# IPMC_MACP.net
KiCad netlist of a schematic drawn in Altium Designer
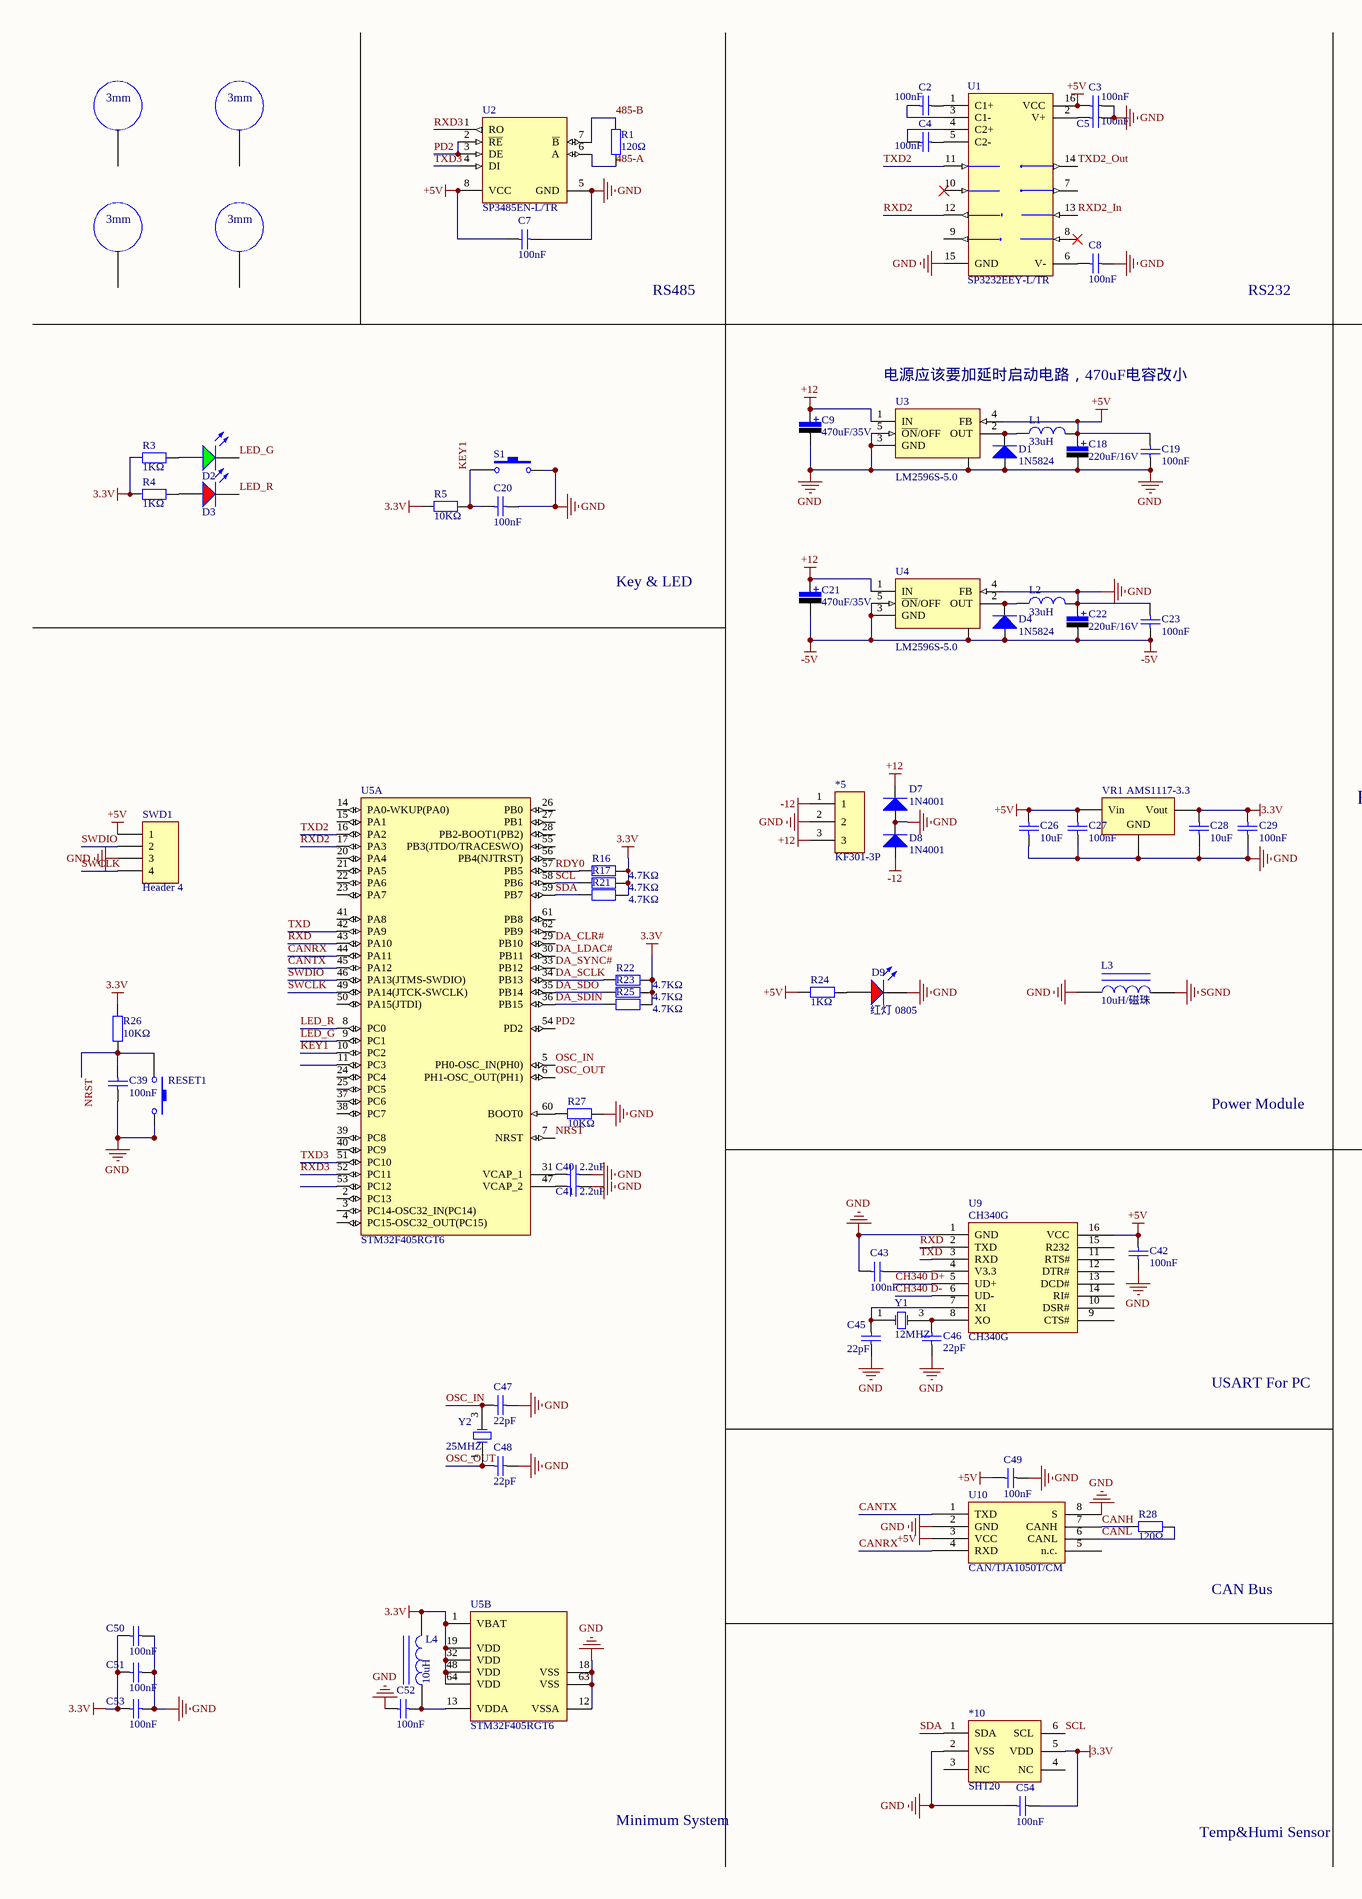
[diagram p0: IPMC_MACP.SchDoc, left]
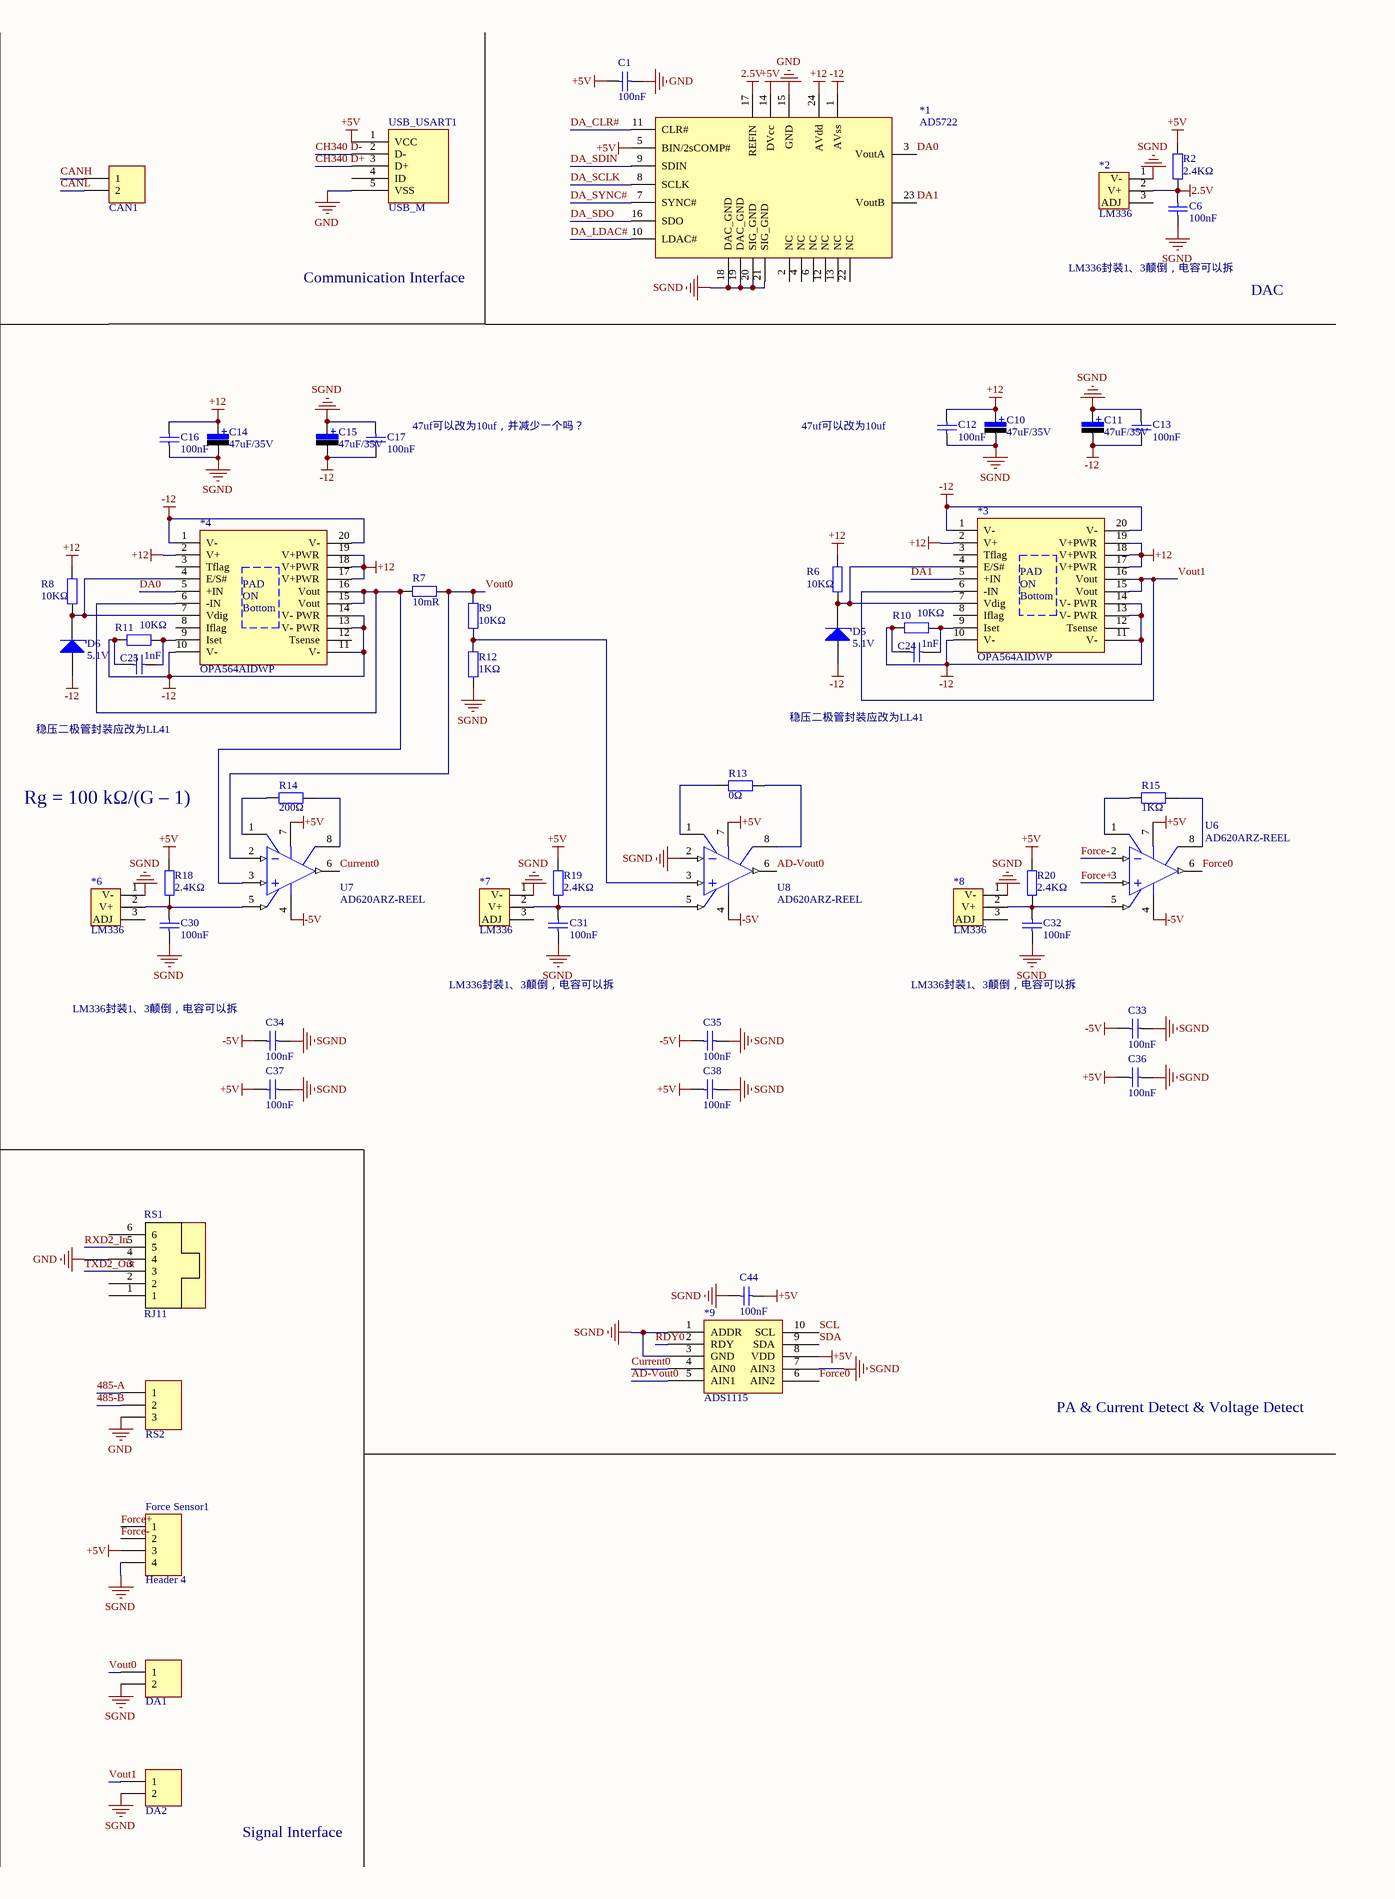
[diagram p1: IPMC_MACP.SchDoc, right]

(export (version "E")
  (design (tool "Eeschema 10.0.6"))
  (components
    (comp (ref "*1")
      (value "AD5722")
      (footprint "TSSOP24P")
      (description "双极性DAC")
      (libsource (lib "fszhang") (part "AD5722"))
    )
    (comp (ref "*2")
      (value "LM336")
      (footprint "TO-92A")
      (description "基准电压芯片2.5/5V")
      (libsource (lib "fszhang") (part "LM336"))
    )
    (comp (ref "*3")
      (value "OPA564AIDWP")
      (footprint "HSOP20")
      (description "PAD on Bottom")
      (libsource (lib "fszhang") (part "OPA564AIDWP"))
    )
    (comp (ref "*4")
      (value "OPA564AIDWP")
      (footprint "HSOP20")
      (description "PAD on Bottom")
      (libsource (lib "fszhang") (part "OPA564AIDWP"))
    )
    (comp (ref "*5")
      (value "KF301-3P")
      (footprint "KF301-3P")
      (description "蓝色端子")
      (libsource (lib "fszhang") (part "KF301-3P"))
    )
    (comp (ref "*6")
      (value "LM336")
      (footprint "TO-92A")
      (description "基准电压芯片2.5/5V")
      (libsource (lib "fszhang") (part "LM336"))
    )
    (comp (ref "*7")
      (value "LM336")
      (footprint "TO-92A")
      (description "基准电压芯片2.5/5V")
      (libsource (lib "fszhang") (part "LM336"))
    )
    (comp (ref "*8")
      (value "LM336")
      (footprint "TO-92A")
      (description "基准电压芯片2.5/5V")
      (libsource (lib "fszhang") (part "LM336"))
    )
    (comp (ref "*9") (value "ADS1115") (footprint "MSOP-UN10_N") (libsource (lib "fszhang") (part "ADS1115")))
    (comp (ref "*10") (value "SHT20") (footprint "DFN6") (libsource (lib "fszhang") (part "SHT20")))
    (comp (ref "C1")
      (value "100nF")
      (footprint "0805_C")
      (description "贴片电容")
      (libsource (lib "Miscellaneous Devices LC") (part "0805 100nF(104) 10% 50V"))
    )
    (comp (ref "C2")
      (value "100nF")
      (footprint "0805_C")
      (description "贴片电容")
      (libsource (lib "Miscellaneous Devices LC") (part "0805 100nF(104) 10% 50V"))
    )
    (comp (ref "C3")
      (value "100nF")
      (footprint "0805_C")
      (description "贴片电容")
      (libsource (lib "Miscellaneous Devices LC") (part "0805 100nF(104) 10% 50V"))
    )
    (comp (ref "C4")
      (value "100nF")
      (footprint "0805_C")
      (description "贴片电容")
      (libsource (lib "Miscellaneous Devices LC") (part "0805 100nF(104) 10% 50V"))
    )
    (comp (ref "C5")
      (value "100nF")
      (footprint "0805_C")
      (description "贴片电容")
      (libsource (lib "Miscellaneous Devices LC") (part "0805 100nF(104) 10% 50V"))
    )
    (comp (ref "C6")
      (value "100nF")
      (footprint "0805_C")
      (description "贴片电容")
      (libsource (lib "Miscellaneous Devices LC") (part "0805 100nF(104) 10% 50V"))
    )
    (comp (ref "C7")
      (value "100nF")
      (footprint "0805_C")
      (description "贴片电容")
      (libsource (lib "Miscellaneous Devices LC") (part "0805 100nF(104) 10% 50V"))
    )
    (comp (ref "C8")
      (value "100nF")
      (footprint "0805_C")
      (description "贴片电容")
      (libsource (lib "Miscellaneous Devices LC") (part "0805 100nF(104) 10% 50V"))
    )
    (comp (ref "C9")
      (value "470uF/35V")
      (footprint "C-RB-S10")
      (description "极性电解电容")
      (fields (field (name "PUBLISHER") "Altium Limited"))
      (libsource (lib "fszhang") (part "Cap Pol"))
    )
    (comp (ref "C10")
      (value "47uF/35V")
      (footprint "C-RB-S6")
      (description "极性电解电容")
      (fields (field (name "PUBLISHER") "Altium Limited"))
      (libsource (lib "fszhang") (part "Cap Pol"))
    )
    (comp (ref "C11")
      (value "47uF/35V")
      (footprint "C-RB-S6")
      (description "极性电解电容")
      (fields (field (name "PUBLISHER") "Altium Limited"))
      (libsource (lib "fszhang") (part "Cap Pol"))
    )
    (comp (ref "C12")
      (value "100nF")
      (footprint "0805_C")
      (description "贴片电容")
      (libsource (lib "Miscellaneous Devices LC") (part "0805 100nF(104) 10% 50V"))
    )
    (comp (ref "C13")
      (value "100nF")
      (footprint "0805_C")
      (description "贴片电容")
      (libsource (lib "Miscellaneous Devices LC") (part "0805 100nF(104) 10% 50V"))
    )
    (comp (ref "C14")
      (value "47uF/35V")
      (footprint "C-RB-S6")
      (description "极性电解电容")
      (fields (field (name "PUBLISHER") "Altium Limited"))
      (libsource (lib "fszhang") (part "Cap Pol"))
    )
    (comp (ref "C15")
      (value "47uF/35V")
      (footprint "C-RB-S6")
      (description "极性电解电容")
      (fields (field (name "PUBLISHER") "Altium Limited"))
      (libsource (lib "fszhang") (part "Cap Pol"))
    )
    (comp (ref "C16")
      (value "100nF")
      (footprint "0805_C")
      (description "贴片电容")
      (libsource (lib "Miscellaneous Devices LC") (part "0805 100nF(104) 10% 50V"))
    )
    (comp (ref "C17")
      (value "100nF")
      (footprint "0805_C")
      (description "贴片电容")
      (libsource (lib "Miscellaneous Devices LC") (part "0805 100nF(104) 10% 50V"))
    )
    (comp (ref "C18")
      (value "220uF/16V")
      (footprint "C-RB-S6")
      (description "极性电解电容")
      (fields (field (name "PUBLISHER") "Altium Limited"))
      (libsource (lib "fszhang") (part "Cap Pol"))
    )
    (comp (ref "C19")
      (value "100nF")
      (footprint "0805_C")
      (description "贴片电容")
      (libsource (lib "Miscellaneous Devices LC") (part "0805 100nF(104) 10% 50V"))
    )
    (comp (ref "C20")
      (value "100nF")
      (footprint "0805_C")
      (description "贴片电容")
      (libsource (lib "Miscellaneous Devices LC") (part "0805 100nF(104) 10% 50V"))
    )
    (comp (ref "C21")
      (value "470uF/35V")
      (footprint "C-RB-S10")
      (description "极性电解电容")
      (fields (field (name "PUBLISHER") "Altium Limited"))
      (libsource (lib "fszhang") (part "Cap Pol"))
    )
    (comp (ref "C22")
      (value "220uF/16V")
      (footprint "C-RB-S6")
      (description "极性电解电容")
      (fields (field (name "PUBLISHER") "Altium Limited"))
      (libsource (lib "fszhang") (part "Cap Pol"))
    )
    (comp (ref "C23")
      (value "100nF")
      (footprint "0805_C")
      (description "贴片电容")
      (libsource (lib "Miscellaneous Devices LC") (part "0805 100nF(104) 10% 50V"))
    )
    (comp (ref "C24")
      (value "1nF")
      (footprint "0805_C")
      (description "贴片电容")
      (libsource (lib "Miscellaneous Devices LC") (part "0805 1nF (102) 10% 50V"))
    )
    (comp (ref "C25")
      (value "1nF")
      (footprint "0805_C")
      (description "贴片电容")
      (libsource (lib "Miscellaneous Devices LC") (part "0805 1nF (102) 10% 50V"))
    )
    (comp (ref "C26")
      (value "10uF")
      (footprint "0805_C")
      (description "贴片电容")
      (libsource (lib "Miscellaneous Devices LC") (part "0805 10uF (106) 10% 25V"))
    )
    (comp (ref "C27")
      (value "100nF")
      (footprint "0805_C")
      (description "贴片电容")
      (libsource (lib "Miscellaneous Devices LC") (part "0805 100nF(104) 10% 50V"))
    )
    (comp (ref "C28")
      (value "10uF")
      (footprint "0805_C")
      (description "贴片电容")
      (libsource (lib "Miscellaneous Devices LC") (part "0805 10uF (106) 10% 25V"))
    )
    (comp (ref "C29")
      (value "100nF")
      (footprint "0805_C")
      (description "贴片电容")
      (libsource (lib "Miscellaneous Devices LC") (part "0805 100nF(104) 10% 50V"))
    )
    (comp (ref "C30")
      (value "100nF")
      (footprint "0805_C")
      (description "贴片电容")
      (libsource (lib "Miscellaneous Devices LC") (part "0805 100nF(104) 10% 50V"))
    )
    (comp (ref "C31")
      (value "100nF")
      (footprint "0805_C")
      (description "贴片电容")
      (libsource (lib "Miscellaneous Devices LC") (part "0805 100nF(104) 10% 50V"))
    )
    (comp (ref "C32")
      (value "100nF")
      (footprint "0805_C")
      (description "贴片电容")
      (libsource (lib "Miscellaneous Devices LC") (part "0805 100nF(104) 10% 50V"))
    )
    (comp (ref "C33")
      (value "100nF")
      (footprint "0805_C")
      (description "贴片电容")
      (libsource (lib "Miscellaneous Devices LC") (part "0805 100nF(104) 10% 50V"))
    )
    (comp (ref "C34")
      (value "100nF")
      (footprint "0805_C")
      (description "贴片电容")
      (libsource (lib "Miscellaneous Devices LC") (part "0805 100nF(104) 10% 50V"))
    )
    (comp (ref "C35")
      (value "100nF")
      (footprint "0805_C")
      (description "贴片电容")
      (libsource (lib "Miscellaneous Devices LC") (part "0805 100nF(104) 10% 50V"))
    )
    (comp (ref "C36")
      (value "100nF")
      (footprint "0805_C")
      (description "贴片电容")
      (libsource (lib "Miscellaneous Devices LC") (part "0805 100nF(104) 10% 50V"))
    )
    (comp (ref "C37")
      (value "100nF")
      (footprint "0805_C")
      (description "贴片电容")
      (libsource (lib "Miscellaneous Devices LC") (part "0805 100nF(104) 10% 50V"))
    )
    (comp (ref "C38")
      (value "100nF")
      (footprint "0805_C")
      (description "贴片电容")
      (libsource (lib "Miscellaneous Devices LC") (part "0805 100nF(104) 10% 50V"))
    )
    (comp (ref "C39")
      (value "100nF")
      (footprint "0805_C")
      (description "贴片电容")
      (libsource (lib "Miscellaneous Devices LC") (part "0805 100nF(104) 10% 50V"))
    )
    (comp (ref "C40")
      (value "2.2uF")
      (footprint "0805_C")
      (description "贴片电容")
      (libsource (lib "Miscellaneous Devices LC") (part "0805 2.2uF (225) 20% 50V"))
    )
    (comp (ref "C41")
      (value "2.2uF")
      (footprint "0805_C")
      (description "贴片电容")
      (libsource (lib "Miscellaneous Devices LC") (part "0805 2.2uF (225) 20% 50V"))
    )
    (comp (ref "C42")
      (value "100nF")
      (footprint "0805_C")
      (description "贴片电容")
      (libsource (lib "Miscellaneous Devices LC") (part "0805 100nF(104) 10% 50V"))
    )
    (comp (ref "C43")
      (value "100nF")
      (footprint "0805_C")
      (description "贴片电容")
      (libsource (lib "Miscellaneous Devices LC") (part "0805 100nF(104) 10% 50V"))
    )
    (comp (ref "C44")
      (value "100nF")
      (footprint "0805_C")
      (description "贴片电容")
      (libsource (lib "Miscellaneous Devices LC") (part "0805 100nF(104) 10% 50V"))
    )
    (comp (ref "C45")
      (value "22pF")
      (footprint "0805_C")
      (description "贴片电容")
      (libsource (lib "Miscellaneous Devices LC") (part "0805 22pF (220) 5% 50V"))
    )
    (comp (ref "C46")
      (value "22pF")
      (footprint "0805_C")
      (description "贴片电容")
      (libsource (lib "Miscellaneous Devices LC") (part "0805 22pF (220) 5% 50V"))
    )
    (comp (ref "C47")
      (value "22pF")
      (footprint "0805_C")
      (description "贴片电容")
      (libsource (lib "Miscellaneous Devices LC") (part "0805 22pF (220) 5% 50V"))
    )
    (comp (ref "C48")
      (value "22pF")
      (footprint "0805_C")
      (description "贴片电容")
      (libsource (lib "Miscellaneous Devices LC") (part "0805 22pF (220) 5% 50V"))
    )
    (comp (ref "C49")
      (value "100nF")
      (footprint "0805_C")
      (description "贴片电容")
      (libsource (lib "Miscellaneous Devices LC") (part "0805 100nF(104) 10% 50V"))
    )
    (comp (ref "C50")
      (value "100nF")
      (footprint "0805_C")
      (description "贴片电容")
      (libsource (lib "Miscellaneous Devices LC") (part "0805 100nF(104) 10% 50V"))
    )
    (comp (ref "C51")
      (value "100nF")
      (footprint "0805_C")
      (description "贴片电容")
      (libsource (lib "Miscellaneous Devices LC") (part "0805 100nF(104) 10% 50V"))
    )
    (comp (ref "C52")
      (value "100nF")
      (footprint "0805_C")
      (description "贴片电容")
      (libsource (lib "Miscellaneous Devices LC") (part "0805 100nF(104) 10% 50V"))
    )
    (comp (ref "C53")
      (value "100nF")
      (footprint "0805_C")
      (description "贴片电容")
      (libsource (lib "Miscellaneous Devices LC") (part "0805 100nF(104) 10% 50V"))
    )
    (comp (ref "C54")
      (value "100nF")
      (footprint "0805_C")
      (description "贴片电容")
      (libsource (lib "Miscellaneous Devices LC") (part "0805 100nF(104) 10% 50V"))
    )
    (comp (ref "CAN1")
      (value "Header 2")
      (footprint "HDR2X1_B1")
      (description "接插件")
      (fields (field (name "PUBLISHER") "Altium Limited"))
      (libsource (lib "fszhang") (part "Header 2"))
    )
    (comp (ref "D1")
      (value "1N5824")
      (footprint "DIODE-SMA")
      (description "二极管")
      (fields (field (name "PUBLISHER") "Altium Limited"))
      (libsource (lib "fszhang") (part "Diode"))
    )
    (comp (ref "D2")
      (value "翠绿 0805")
      (footprint "0805_LED_S1")
      (description "发光二极管")
      (libsource (lib "Miscellaneous Devices LC") (part "0805 翠绿"))
    )
    (comp (ref "D3")
      (value "红灯 0805")
      (footprint "0805_LED_S1")
      (description "发光二极管")
      (libsource (lib "Miscellaneous Devices LC") (part "0805 红灯"))
    )
    (comp (ref "D4")
      (value "1N5824")
      (footprint "DIODE-SMA")
      (description "二极管")
      (fields (field (name "PUBLISHER") "Altium Limited"))
      (libsource (lib "fszhang") (part "Diode"))
    )
    (comp (ref "D5")
      (value "5.1V")
      (footprint "DIODE-1206")
      (description "稳压二极管")
      (fields (field (name "PUBLISHER") "Altium Limited"))
      (libsource (lib "fszhang") (part "Diode-Z"))
    )
    (comp (ref "D6")
      (value "5.1V")
      (footprint "DIODE-1206")
      (description "稳压二极管")
      (fields (field (name "PUBLISHER") "Altium Limited"))
      (libsource (lib "fszhang") (part "Diode-Z"))
    )
    (comp (ref "D7")
      (value "1N4001")
      (footprint "DIODE-SMA")
      (description "二极管")
      (fields (field (name "PUBLISHER") "Altium Limited"))
      (libsource (lib "fszhang") (part "Diode"))
    )
    (comp (ref "D8")
      (value "1N4001")
      (footprint "DIODE-SMA")
      (description "二极管")
      (fields (field (name "PUBLISHER") "Altium Limited"))
      (libsource (lib "fszhang") (part "Diode"))
    )
    (comp (ref "D9")
      (value "红灯 0805")
      (footprint "0805_LED_S1")
      (description "发光二极管")
      (libsource (lib "Miscellaneous Devices LC") (part "0805 红灯"))
    )
    (comp (ref "DA1")
      (value "Header 2")
      (footprint "HDR2X1_B1")
      (description "接插件")
      (fields (field (name "PUBLISHER") "Altium Limited"))
      (libsource (lib "fszhang") (part "Header 2"))
    )
    (comp (ref "DA2")
      (value "Header 2")
      (footprint "HDR2X1_B1")
      (description "接插件")
      (fields (field (name "PUBLISHER") "Altium Limited"))
      (libsource (lib "fszhang") (part "Header 2"))
    )
    (comp (ref "Force Sensor1")
      (value "Header 4")
      (footprint "fszhang:HDR4X1_B1")
      (description "Header, 4-Pin")
      (fields (field (name "PUBLISHER") "Altium Limited"))
      (libsource (lib "Miscellaneous Connectors") (part "Header 4"))
    )
    (comp (ref "L1")
      (value "33uH")
      (footprint "L-SMD-12")
      (description "电感")
      (fields (field (name "PUBLISHER") "Altium Limited"))
      (libsource (lib "fszhang") (part "Inductor"))
    )
    (comp (ref "L2")
      (value "33uH")
      (footprint "L-SMD-12")
      (description "电感")
      (fields (field (name "PUBLISHER") "Altium Limited"))
      (libsource (lib "fszhang") (part "Inductor"))
    )
    (comp (ref "L3")
      (value "10uH/磁珠")
      (footprint "0805_L")
      (description "贴片电感")
      (libsource (lib "Miscellaneous Devices LC") (part "0805 10uH 10%"))
    )
    (comp (ref "L4")
      (value "10uH")
      (footprint "0805_L")
      (description "贴片电感")
      (libsource (lib "Miscellaneous Devices LC") (part "0805 10uH 10%"))
    )
    (comp (ref "R1")
      (value "120Ω")
      (footprint "0805_R")
      (description "贴片电阻")
      (libsource (lib "Miscellaneous Devices LC") (part "0805 120Ω (1200) 1%"))
    )
    (comp (ref "R2")
      (value "2.4KΩ")
      (footprint "0805_R")
      (description "贴片电阻")
      (libsource (lib "Miscellaneous Devices LC") (part "0805 2.4KΩ (2401) 1%"))
    )
    (comp (ref "R3")
      (value "1KΩ")
      (footprint "0805_R")
      (description "贴片电阻")
      (libsource (lib "Miscellaneous Devices LC") (part "0805 1KΩ (1001) 1%"))
    )
    (comp (ref "R4")
      (value "1KΩ")
      (footprint "0805_R")
      (description "贴片电阻")
      (libsource (lib "Miscellaneous Devices LC") (part "0805 1KΩ (1001) 1%"))
    )
    (comp (ref "R5")
      (value "10KΩ")
      (footprint "0805_R")
      (description "贴片电阻")
      (libsource (lib "") (part "0805 10KΩ (1002) 1%_1"))
    )
    (comp (ref "R6")
      (value "10KΩ")
      (footprint "0805_R")
      (description "贴片电阻")
      (libsource (lib "Miscellaneous Devices LC") (part "0805 10KΩ (1002) 1%"))
    )
    (comp (ref "R7")
      (value "10mR")
      (footprint "2512")
      (description "贴片电阻")
      (fields (field (name "PUBLISHER") "Altium Limited"))
      (libsource (lib "fszhang") (part "Res1"))
    )
    (comp (ref "R8")
      (value "10KΩ")
      (footprint "0805_R")
      (description "贴片电阻")
      (libsource (lib "Miscellaneous Devices LC") (part "0805 10KΩ (1002) 1%"))
    )
    (comp (ref "R9")
      (value "10KΩ")
      (footprint "0805_R")
      (description "贴片电阻")
      (libsource (lib "Miscellaneous Devices LC") (part "0805 20KΩ (2002) 1%"))
    )
    (comp (ref "R10")
      (value "10KΩ")
      (footprint "0805_R")
      (description "贴片电阻")
      (libsource (lib "") (part "0805 10KΩ (1002) 1%_1"))
    )
    (comp (ref "R11")
      (value "10KΩ")
      (footprint "0805_R")
      (description "贴片电阻")
      (libsource (lib "") (part "0805 10KΩ (1002) 1%_1"))
    )
    (comp (ref "R12")
      (value "1KΩ")
      (footprint "0805_R")
      (description "贴片电阻")
      (libsource (lib "Miscellaneous Devices LC") (part "0805 20KΩ (2002) 1%"))
    )
    (comp (ref "R13")
      (value "0Ω")
      (footprint "0805_R")
      (description "贴片电阻")
      (libsource (lib "Miscellaneous Devices LC") (part "0805 0Ω (0R0) 1%"))
    )
    (comp (ref "R14")
      (value "200Ω")
      (footprint "0805_R")
      (description "贴片电阻")
      (libsource (lib "Miscellaneous Devices LC") (part "0805 200Ω (2000) 1%"))
    )
    (comp (ref "R15")
      (value "1KΩ")
      (footprint "0805_R")
      (description "贴片电阻")
      (libsource (lib "Miscellaneous Devices LC") (part "0805 1KΩ (1001) 1%"))
    )
    (comp (ref "R16")
      (value "4.7KΩ")
      (footprint "0805_R")
      (description "贴片电阻")
      (libsource (lib "Miscellaneous Devices LC") (part "0805 4.7KΩ (4701) 1%"))
    )
    (comp (ref "R17")
      (value "4.7KΩ")
      (footprint "0805_R")
      (description "贴片电阻")
      (libsource (lib "Miscellaneous Devices LC") (part "0805 4.7KΩ (4701) 1%"))
    )
    (comp (ref "R18")
      (value "2.4KΩ")
      (footprint "0805_R")
      (description "贴片电阻")
      (libsource (lib "Miscellaneous Devices LC") (part "0805 2.4KΩ (2401) 1%"))
    )
    (comp (ref "R19")
      (value "2.4KΩ")
      (footprint "0805_R")
      (description "贴片电阻")
      (libsource (lib "Miscellaneous Devices LC") (part "0805 2.4KΩ (2401) 1%"))
    )
    (comp (ref "R20")
      (value "2.4KΩ")
      (footprint "0805_R")
      (description "贴片电阻")
      (libsource (lib "Miscellaneous Devices LC") (part "0805 2.4KΩ (2401) 1%"))
    )
    (comp (ref "R21")
      (value "4.7KΩ")
      (footprint "0805_R")
      (description "贴片电阻")
      (libsource (lib "Miscellaneous Devices LC") (part "0805 4.7KΩ (4701) 1%"))
    )
    (comp (ref "R22")
      (value "4.7KΩ")
      (footprint "0805_R")
      (description "贴片电阻")
      (libsource (lib "Miscellaneous Devices LC") (part "0805 4.7KΩ (4701) 1%"))
    )
    (comp (ref "R23")
      (value "4.7KΩ")
      (footprint "0805_R")
      (description "贴片电阻")
      (libsource (lib "Miscellaneous Devices LC") (part "0805 4.7KΩ (4701) 1%"))
    )
    (comp (ref "R24")
      (value "1KΩ")
      (footprint "0805_R")
      (description "贴片电阻")
      (libsource (lib "Miscellaneous Devices LC") (part "0805 1KΩ (1001) 1%"))
    )
    (comp (ref "R25")
      (value "4.7KΩ")
      (footprint "0805_R")
      (description "贴片电阻")
      (libsource (lib "Miscellaneous Devices LC") (part "0805 4.7KΩ (4701) 1%"))
    )
    (comp (ref "R26")
      (value "10KΩ")
      (footprint "0805_R")
      (description "贴片电阻")
      (libsource (lib "") (part "0805 10KΩ (1002) 1%_2"))
    )
    (comp (ref "R27")
      (value "10KΩ")
      (footprint "0805_R")
      (description "贴片电阻")
      (libsource (lib "") (part "0805 10KΩ (1002) 1%_3"))
    )
    (comp (ref "R28")
      (value "120Ω")
      (footprint "0805_R")
      (description "贴片电阻")
      (libsource (lib "") (part "0805 120Ω (1200) 1%_1"))
    )
    (comp (ref "RESET1")
      (value "SW-PB")
      (footprint "SW_PB2_A1")
      (description "微动开关")
      (fields (field (name "PUBLISHER") "Altium Limited"))
      (libsource (lib "fszhang") (part "SW-PB"))
    )
    (comp (ref "RS1") (value "RJ11") (footprint "RJ6-RJ11") (libsource (lib "fszhang") (part "RJ11")))
    (comp (ref "RS2")
      (value "Header 3")
      (footprint "HDR3X1_B1")
      (description "接插件")
      (fields (field (name "PUBLISHER") "Altium Limited"))
      (libsource (lib "fszhang") (part "Header 3"))
    )
    (comp (ref "S1")
      (value "SW-PB")
      (footprint "SW_PB2_A1")
      (description "微动开关")
      (fields (field (name "PUBLISHER") "Altium Limited"))
      (libsource (lib "fszhang") (part "SW-PB"))
    )
    (comp (ref "SWD1")
      (value "Header 4")
      (footprint "HDR1X4")
      (description "Header, 4-Pin")
      (fields (field (name "PUBLISHER") "Altium Limited"))
      (libsource (lib "Miscellaneous Connectors") (part "Header 4"))
    )
    (comp (ref "T1") (value "M3铜柱螺丝孔") (footprint "螺丝孔-3mm") (libsource (lib "fszhang") (part "M3铜柱螺丝孔")))
    (comp (ref "T2") (value "M3铜柱螺丝孔") (footprint "螺丝孔-3mm") (libsource (lib "fszhang") (part "M3铜柱螺丝孔")))
    (comp (ref "T3") (value "M3铜柱螺丝孔") (footprint "螺丝孔-3mm") (libsource (lib "fszhang") (part "M3铜柱螺丝孔")))
    (comp (ref "T4") (value "M3铜柱螺丝孔") (footprint "螺丝孔-3mm") (libsource (lib "fszhang") (part "M3铜柱螺丝孔")))
    (comp (ref "U1")
      (value "SP3232EEY-L/TR")
      (footprint "TSSOP-16")
      (description "RS232")
      (libsource (lib "Miscellaneous Devices LC") (part "SP3232EEY-L/TR"))
    )
    (comp (ref "U2")
      (value "SP3485EN-L/TR")
      (footprint "SOIC-8_150mil")
      (description "RS-485/RS-422")
      (libsource (lib "Miscellaneous Devices LC") (part "SP3485EN-L/TR"))
    )
    (comp (ref "U3")
      (value "LM2596S-5.0")
      (footprint "TO-263-5")
      (description "5V稳压芯片")
      (fields (field (name "PUBLISHER") "Altium Limited"))
      (libsource (lib "fszhang") (part "LM2596S-5.0"))
    )
    (comp (ref "U4")
      (value "LM2596S-5.0")
      (footprint "TO-263-5")
      (description "5V稳压芯片")
      (fields (field (name "PUBLISHER") "Altium Limited"))
      (libsource (lib "fszhang") (part "LM2596S-5.0"))
    )
    (comp (ref "U5")
      (value "STM32F405RGT6")
      (footprint "STM-LQFP64_L")
      (fields (field (name "MANUFACTURER") "STMicroelectronics"))
      (libsource (lib "STMicroelectronics STM32 F4") (part "STM32F405RGT6"))
    )
    (comp (ref "U6")
      (value "AD620ARZ-REEL")
      (footprint "SOIC-8_150mil")
      (description "仪放")
      (libsource (lib "Miscellaneous Devices LC") (part "AD620ARZ-REEL"))
    )
    (comp (ref "U7")
      (value "AD620ARZ-REEL")
      (footprint "SOIC-8_150mil")
      (description "仪放")
      (libsource (lib "Miscellaneous Devices LC") (part "AD620ARZ-REEL"))
    )
    (comp (ref "U8")
      (value "AD620ARZ-REEL")
      (footprint "SOIC-8_150mil")
      (description "仪放")
      (libsource (lib "Miscellaneous Devices LC") (part "AD620ARZ-REEL"))
    )
    (comp (ref "U9")
      (value "CH340G")
      (footprint "SOIC-16_150mil")
      (description "USB")
      (libsource (lib "Miscellaneous Devices LC") (part "CH340G"))
    )
    (comp (ref "U10")
      (value "CAN/TJA1050T/CM")
      (footprint "SOIC-8_150mil")
      (description "CAN")
      (libsource (lib "Miscellaneous Devices LC") (part "CAN/TJA1050T/CM"))
    )
    (comp (ref "USB_USART1")
      (value "USB_M")
      (footprint "USB_MICRO")
      (description "MicroUSB接口")
      (libsource (lib "fszhang") (part "USB_M"))
    )
    (comp (ref "VR1")
      (value "AMS1117-3.3")
      (footprint "SOT-223")
      (description "低压差线性稳压(LDO)")
      (libsource (lib "Miscellaneous Devices LC") (part "SOT-223 AMS1117-3.3"))
    )
    (comp (ref "Y1")
      (value "12MHZ")
      (footprint "SMD-3225_4P")
      (description "贴片晶振")
      (libsource (lib "Miscellaneous Devices LC") (part "SMD-3225_4P  12MHZ 20PF 10PPM"))
    )
    (comp (ref "Y2")
      (value "25MHZ")
      (footprint "SMD-3225_4P")
      (description "贴片晶振")
      (libsource (lib "Miscellaneous Devices LC") (part "SMD-3225_4P  25MHZ 12PF 10PPM"))
    )
  )
  (nets
    (net (code "1") (name "+5V") (class "Default")
      (node (ref "*1") (pin "14") (pinfunction "DVcc_14") (pintype "passive"))
      (node (ref "*1") (pin "5") (pinfunction "BIN/2sCOMP#_5") (pintype "passive"))
      (node (ref "*9") (pin "8") (pinfunction "VDD_8") (pintype "passive"))
      (node (ref "C1") (pin "2") (pinfunction "2_2") (pintype "passive"))
      (node (ref "C18") (pin "1") (pinfunction "1_1") (pintype "passive"))
      (node (ref "C19") (pin "2") (pinfunction "2_2") (pintype "passive"))
      (node (ref "C26") (pin "2") (pinfunction "2_2") (pintype "passive"))
      (node (ref "C27") (pin "2") (pinfunction "2_2") (pintype "passive"))
      (node (ref "C3") (pin "1") (pinfunction "1_1") (pintype "passive"))
      (node (ref "C36") (pin "2") (pinfunction "2_2") (pintype "passive"))
      (node (ref "C37") (pin "2") (pinfunction "2_2") (pintype "passive"))
      (node (ref "C38") (pin "2") (pinfunction "2_2") (pintype "passive"))
      (node (ref "C42") (pin "2") (pinfunction "2_2") (pintype "passive"))
      (node (ref "C44") (pin "1") (pinfunction "1_1") (pintype "passive"))
      (node (ref "C49") (pin "2") (pinfunction "2_2") (pintype "passive"))
      (node (ref "C7") (pin "2") (pinfunction "2_2") (pintype "passive"))
      (node (ref "Force Sensor1") (pin "3") (pinfunction "3_3") (pintype "passive"))
      (node (ref "L1") (pin "2") (pinfunction "2_2") (pintype "passive"))
      (node (ref "R18") (pin "2") (pinfunction "2_2") (pintype "passive"))
      (node (ref "R19") (pin "2") (pinfunction "2_2") (pintype "passive"))
      (node (ref "R2") (pin "2") (pinfunction "2_2") (pintype "passive"))
      (node (ref "R20") (pin "2") (pinfunction "2_2") (pintype "passive"))
      (node (ref "R24") (pin "1") (pinfunction "1_1") (pintype "passive"))
      (node (ref "SWD1") (pin "1") (pinfunction "1_1") (pintype "passive"))
      (node (ref "U1") (pin "16") (pinfunction "VCC_16") (pintype "power_in"))
      (node (ref "U10") (pin "3") (pinfunction "VCC_3") (pintype "passive"))
      (node (ref "U2") (pin "8") (pinfunction "VCC_8") (pintype "power_in"))
      (node (ref "U3") (pin "4") (pinfunction "FB_4") (pintype "input"))
      (node (ref "U6") (pin "7") (pinfunction "V+_7") (pintype "power_in"))
      (node (ref "U7") (pin "7") (pinfunction "V+_7") (pintype "power_in"))
      (node (ref "U8") (pin "7") (pinfunction "V+_7") (pintype "power_in"))
      (node (ref "U9") (pin "16") (pinfunction "VCC_16") (pintype "passive"))
      (node (ref "USB_USART1") (pin "1") (pinfunction "VCC_1") (pintype "passive"))
      (node (ref "VR1") (pin "3") (pinfunction "Vin_3") (pintype "passive"))
    )
    (net (code "2") (name "+12") (class "Default")
      (node (ref "*1") (pin "24") (pinfunction "AVdd_24") (pintype "passive"))
      (node (ref "*3") (pin "17") (pinfunction "V+PWR_17") (pintype "passive"))
      (node (ref "*3") (pin "18") (pinfunction "V+PWR_18") (pintype "passive"))
      (node (ref "*3") (pin "19") (pinfunction "V+PWR_19") (pintype "passive"))
      (node (ref "*3") (pin "2") (pinfunction "V+_2") (pintype "passive"))
      (node (ref "*4") (pin "17") (pinfunction "V+PWR_17") (pintype "passive"))
      (node (ref "*4") (pin "18") (pinfunction "V+PWR_18") (pintype "passive"))
      (node (ref "*4") (pin "19") (pinfunction "V+PWR_19") (pintype "passive"))
      (node (ref "*4") (pin "2") (pinfunction "V+_2") (pintype "passive"))
      (node (ref "*5") (pin "3") (pinfunction "3_3") (pintype "passive"))
      (node (ref "C10") (pin "1") (pinfunction "1_1") (pintype "passive"))
      (node (ref "C12") (pin "2") (pinfunction "2_2") (pintype "passive"))
      (node (ref "C14") (pin "1") (pinfunction "1_1") (pintype "passive"))
      (node (ref "C16") (pin "2") (pinfunction "2_2") (pintype "passive"))
      (node (ref "C21") (pin "1") (pinfunction "1_1") (pintype "passive"))
      (node (ref "C9") (pin "1") (pinfunction "1_1") (pintype "passive"))
      (node (ref "D7") (pin "2") (pinfunction "K_2") (pintype "passive"))
      (node (ref "R6") (pin "2") (pinfunction "2_2") (pintype "passive"))
      (node (ref "R8") (pin "2") (pinfunction "2_2") (pintype "passive"))
      (node (ref "U3") (pin "1") (pinfunction "IN_1") (pintype "power_in"))
      (node (ref "U4") (pin "1") (pinfunction "IN_1") (pintype "power_in"))
    )
    (net (code "3") (name "-5V") (class "Default")
      (node (ref "C21") (pin "2") (pinfunction "2_2") (pintype "passive"))
      (node (ref "C22") (pin "2") (pinfunction "2_2") (pintype "passive"))
      (node (ref "C23") (pin "1") (pinfunction "1_1") (pintype "passive"))
      (node (ref "C33") (pin "2") (pinfunction "2_2") (pintype "passive"))
      (node (ref "C34") (pin "2") (pinfunction "2_2") (pintype "passive"))
      (node (ref "C35") (pin "2") (pinfunction "2_2") (pintype "passive"))
      (node (ref "D4") (pin "1") (pinfunction "A_1") (pintype "passive"))
      (node (ref "U4") (pin "3") (pinfunction "GND_3") (pintype "power_in"))
      (node (ref "U4") (pin "5") (pinfunction "~{ON}/OFF_5") (pintype "input"))
      (node (ref "U4") (pin "6") (pinfunction "6_6") (pintype "power_in"))
      (node (ref "U6") (pin "4") (pinfunction "V-_4") (pintype "power_in"))
      (node (ref "U7") (pin "4") (pinfunction "V-_4") (pintype "power_in"))
      (node (ref "U8") (pin "4") (pinfunction "V-_4") (pintype "power_in"))
    )
    (net (code "4") (name "-12") (class "Default")
      (node (ref "*1") (pin "1") (pinfunction "AVss_1") (pintype "passive"))
      (node (ref "*3") (pin "1") (pinfunction "V-_1") (pintype "passive"))
      (node (ref "*3") (pin "10") (pinfunction "V-_10") (pintype "passive"))
      (node (ref "*3") (pin "11") (pinfunction "V-_11") (pintype "passive"))
      (node (ref "*3") (pin "13") (pinfunction "V-_PWR_13") (pintype "passive"))
      (node (ref "*3") (pin "14") (pinfunction "V-_PWR_14") (pintype "passive"))
      (node (ref "*3") (pin "20") (pinfunction "V-_20") (pintype "passive"))
      (node (ref "*4") (pin "1") (pinfunction "V-_1") (pintype "passive"))
      (node (ref "*4") (pin "10") (pinfunction "V-_10") (pintype "passive"))
      (node (ref "*4") (pin "11") (pinfunction "V-_11") (pintype "passive"))
      (node (ref "*4") (pin "13") (pinfunction "V-_PWR_13") (pintype "passive"))
      (node (ref "*4") (pin "14") (pinfunction "V-_PWR_14") (pintype "passive"))
      (node (ref "*4") (pin "20") (pinfunction "V-_20") (pintype "passive"))
      (node (ref "*5") (pin "1") (pinfunction "1_1") (pintype "passive"))
      (node (ref "C11") (pin "2") (pinfunction "2_2") (pintype "passive"))
      (node (ref "C13") (pin "2") (pinfunction "2_2") (pintype "passive"))
      (node (ref "C15") (pin "2") (pinfunction "2_2") (pintype "passive"))
      (node (ref "C17") (pin "2") (pinfunction "2_2") (pintype "passive"))
      (node (ref "C24") (pin "1") (pinfunction "1_1") (pintype "passive"))
      (node (ref "C25") (pin "1") (pinfunction "1_1") (pintype "passive"))
      (node (ref "D5") (pin "1") (pinfunction "A_1") (pintype "passive"))
      (node (ref "D6") (pin "1") (pinfunction "A_1") (pintype "passive"))
      (node (ref "D8") (pin "1") (pinfunction "A_1") (pintype "passive"))
      (node (ref "R10") (pin "1") (pinfunction "1_1") (pintype "passive"))
      (node (ref "R11") (pin "1") (pinfunction "1_1") (pintype "passive"))
    )
    (net (code "5") (name "/485-A") (class "Default")
      (node (ref "R1") (pin "1") (pinfunction "1_1") (pintype "passive"))
      (node (ref "RS2") (pin "1") (pinfunction "1_1") (pintype "passive"))
      (node (ref "U2") (pin "6") (pinfunction "A_6") (pintype "bidirectional"))
    )
    (net (code "6") (name "/485-B") (class "Default")
      (node (ref "R1") (pin "2") (pinfunction "2_2") (pintype "passive"))
      (node (ref "RS2") (pin "2") (pinfunction "2_2") (pintype "passive"))
      (node (ref "U2") (pin "7") (pinfunction "~{B}_7") (pintype "bidirectional"))
    )
    (net (code "7") (name "/AD-Vout0") (class "Default")
      (node (ref "*9") (pin "5") (pinfunction "AIN1_5") (pintype "passive"))
      (node (ref "U8") (pin "6") (pinfunction "OUT_6") (pintype "output"))
    )
    (net (code "8") (name "/CANH") (class "Default")
      (node (ref "CAN1") (pin "1") (pinfunction "1_1") (pintype "passive"))
      (node (ref "R28") (pin "1") (pinfunction "1_1") (pintype "passive"))
      (node (ref "U10") (pin "7") (pinfunction "CANH_7") (pintype "passive"))
    )
    (net (code "9") (name "/CANL") (class "Default")
      (node (ref "CAN1") (pin "2") (pinfunction "2_2") (pintype "passive"))
      (node (ref "R28") (pin "2") (pinfunction "2_2") (pintype "passive"))
      (node (ref "U10") (pin "6") (pinfunction "CANL_6") (pintype "passive"))
    )
    (net (code "10") (name "/CANRX") (class "Default")
      (node (ref "U10") (pin "4") (pinfunction "RXD_4") (pintype "passive"))
      (node (ref "U5") (pin "44") (pinfunction "PA11_44") (pintype "bidirectional"))
    )
    (net (code "11") (name "/CANTX") (class "Default")
      (node (ref "U10") (pin "1") (pinfunction "TXD_1") (pintype "passive"))
      (node (ref "U5") (pin "45") (pinfunction "PA12_45") (pintype "bidirectional"))
    )
    (net (code "12") (name "/CH340 D+") (class "Default")
      (node (ref "U9") (pin "5") (pinfunction "UD+_5") (pintype "passive"))
      (node (ref "USB_USART1") (pin "3") (pinfunction "D+_3") (pintype "passive"))
    )
    (net (code "13") (name "/CH340 D-") (class "Default")
      (node (ref "U9") (pin "6") (pinfunction "UD-_6") (pintype "passive"))
      (node (ref "USB_USART1") (pin "2") (pinfunction "D-_2") (pintype "passive"))
    )
    (net (code "14") (name "/Current0") (class "Default")
      (node (ref "*9") (pin "4") (pinfunction "AIN0_4") (pintype "passive"))
      (node (ref "U7") (pin "6") (pinfunction "OUT_6") (pintype "output"))
    )
    (net (code "15") (name "/DA0") (class "Default")
      (node (ref "*1") (pin "3") (pinfunction "VoutA_3") (pintype "passive"))
      (node (ref "*4") (pin "5") (pinfunction "+IN_5") (pintype "passive"))
    )
    (net (code "16") (name "/DA1") (class "Default")
      (node (ref "*1") (pin "23") (pinfunction "VoutB_23") (pintype "passive"))
      (node (ref "*3") (pin "5") (pinfunction "+IN_5") (pintype "passive"))
    )
    (net (code "17") (name "/DA_CLR#") (class "Default")
      (node (ref "*1") (pin "11") (pinfunction "CLR#_11") (pintype "passive"))
      (node (ref "U5") (pin "29") (pinfunction "PB10_29") (pintype "bidirectional"))
    )
    (net (code "18") (name "/DA_LDAC#") (class "Default")
      (node (ref "*1") (pin "10") (pinfunction "LDAC#_10") (pintype "passive"))
      (node (ref "U5") (pin "30") (pinfunction "PB11_30") (pintype "bidirectional"))
    )
    (net (code "19") (name "/DA_SCLK") (class "Default")
      (node (ref "*1") (pin "8") (pinfunction "SCLK_8") (pintype "passive"))
      (node (ref "R22") (pin "1") (pinfunction "1_1") (pintype "passive"))
      (node (ref "U5") (pin "34") (pinfunction "PB13_34") (pintype "bidirectional"))
    )
    (net (code "20") (name "/DA_SDIN") (class "Default")
      (node (ref "*1") (pin "9") (pinfunction "SDIN_9") (pintype "passive"))
      (node (ref "R25") (pin "1") (pinfunction "1_1") (pintype "passive"))
      (node (ref "U5") (pin "36") (pinfunction "PB15_36") (pintype "bidirectional"))
    )
    (net (code "21") (name "/DA_SDO") (class "Default")
      (node (ref "*1") (pin "16") (pinfunction "SDO_16") (pintype "passive"))
      (node (ref "R23") (pin "1") (pinfunction "1_1") (pintype "passive"))
      (node (ref "U5") (pin "35") (pinfunction "PB14_35") (pintype "bidirectional"))
    )
    (net (code "22") (name "/DA_SYNC#") (class "Default")
      (node (ref "*1") (pin "7") (pinfunction "SYNC#_7") (pintype "passive"))
      (node (ref "U5") (pin "33") (pinfunction "PB12_33") (pintype "bidirectional"))
    )
    (net (code "23") (name "/Force+") (class "Default")
      (node (ref "Force Sensor1") (pin "1") (pinfunction "1_1") (pintype "passive"))
      (node (ref "U6") (pin "3") (pinfunction "+IN_3") (pintype "input"))
    )
    (net (code "24") (name "/Force-") (class "Default")
      (node (ref "Force Sensor1") (pin "2") (pinfunction "2_2") (pintype "passive"))
      (node (ref "U6") (pin "2") (pinfunction "-IN_2") (pintype "input"))
    )
    (net (code "25") (name "/Force0") (class "Default")
      (node (ref "*9") (pin "6") (pinfunction "AIN2_6") (pintype "passive"))
      (node (ref "U6") (pin "6") (pinfunction "OUT_6") (pintype "output"))
    )
    (net (code "26") (name "/KEY1") (class "Default")
      (node (ref "C20") (pin "1") (pinfunction "1_1") (pintype "passive"))
      (node (ref "R5") (pin "2") (pinfunction "2_2") (pintype "passive"))
      (node (ref "S1") (pin "1") (pinfunction "1_1") (pintype "passive"))
      (node (ref "U5") (pin "10") (pinfunction "PC2_10") (pintype "bidirectional"))
    )
    (net (code "27") (name "/LED_G") (class "Default")
      (node (ref "D2") (pin "K") (pinfunction "K_K") (pintype "passive"))
      (node (ref "U5") (pin "9") (pinfunction "PC1_9") (pintype "bidirectional"))
    )
    (net (code "28") (name "/LED_R") (class "Default")
      (node (ref "D3") (pin "K") (pinfunction "K_K") (pintype "passive"))
      (node (ref "U5") (pin "8") (pinfunction "PC0_8") (pintype "bidirectional"))
    )
    (net (code "29") (name "/NRST") (class "Default")
      (node (ref "C39") (pin "1") (pinfunction "1_1") (pintype "passive"))
      (node (ref "R26") (pin "2") (pinfunction "2_2") (pintype "passive"))
      (node (ref "RESET1") (pin "1") (pinfunction "1_1") (pintype "passive"))
      (node (ref "U5") (pin "7") (pinfunction "NRST_7") (pintype "bidirectional"))
    )
    (net (code "30") (name "/OSC_IN") (class "Default")
      (node (ref "C47") (pin "2") (pinfunction "2_2") (pintype "passive"))
      (node (ref "U5") (pin "5") (pinfunction "PH0-OSC_IN(PH0)_5") (pintype "bidirectional"))
      (node (ref "Y2") (pin "3") (pinfunction "OSC2_3") (pintype "passive"))
    )
    (net (code "31") (name "/OSC_OUT") (class "Default")
      (node (ref "C48") (pin "2") (pinfunction "2_2") (pintype "passive"))
      (node (ref "U5") (pin "6") (pinfunction "PH1-OSC_OUT(PH1)_6") (pintype "bidirectional"))
      (node (ref "Y2") (pin "1") (pinfunction "OSC1_1") (pintype "passive"))
    )
    (net (code "32") (name "/PD2") (class "Default")
      (node (ref "U2") (pin "2") (pinfunction "~{RE}_2") (pintype "input"))
      (node (ref "U2") (pin "3") (pinfunction "DE_3") (pintype "input"))
      (node (ref "U5") (pin "54") (pinfunction "PD2_54") (pintype "bidirectional"))
    )
    (net (code "33") (name "/RDY0") (class "Default")
      (node (ref "*9") (pin "2") (pinfunction "RDY_2") (pintype "passive"))
      (node (ref "R16") (pin "1") (pinfunction "1_1") (pintype "passive"))
      (node (ref "U5") (pin "57") (pinfunction "PB5_57") (pintype "bidirectional"))
    )
    (net (code "34") (name "/RXD") (class "Default")
      (node (ref "U5") (pin "43") (pinfunction "PA10_43") (pintype "bidirectional"))
      (node (ref "U9") (pin "2") (pinfunction "TXD_2") (pintype "passive"))
    )
    (net (code "35") (name "/RXD2") (class "Default")
      (node (ref "U1") (pin "12") (pinfunction "R1OUT_12") (pintype "output"))
      (node (ref "U5") (pin "17") (pinfunction "PA3_17") (pintype "bidirectional"))
    )
    (net (code "36") (name "/RXD2_In") (class "Default")
      (node (ref "RS1") (pin "5") (pinfunction "5_5") (pintype "passive"))
      (node (ref "U1") (pin "13") (pinfunction "R1IN_13") (pintype "input"))
    )
    (net (code "37") (name "/RXD3") (class "Default")
      (node (ref "U2") (pin "1") (pinfunction "RO_1") (pintype "output"))
      (node (ref "U5") (pin "52") (pinfunction "PC11_52") (pintype "bidirectional"))
    )
    (net (code "38") (name "/SCL") (class "Default")
      (node (ref "*10") (pin "6") (pinfunction "SCL_6") (pintype "passive"))
      (node (ref "*9") (pin "10") (pinfunction "SCL_10") (pintype "passive"))
      (node (ref "R17") (pin "1") (pinfunction "1_1") (pintype "passive"))
      (node (ref "U5") (pin "58") (pinfunction "PB6_58") (pintype "bidirectional"))
    )
    (net (code "39") (name "/SDA") (class "Default")
      (node (ref "*10") (pin "1") (pinfunction "SDA_1") (pintype "passive"))
      (node (ref "*9") (pin "9") (pinfunction "SDA_9") (pintype "passive"))
      (node (ref "R21") (pin "1") (pinfunction "1_1") (pintype "passive"))
      (node (ref "U5") (pin "59") (pinfunction "PB7_59") (pintype "bidirectional"))
    )
    (net (code "40") (name "/SWCLK") (class "Default")
      (node (ref "SWD1") (pin "4") (pinfunction "4_4") (pintype "passive"))
      (node (ref "U5") (pin "49") (pinfunction "PA14(JTCK-SWCLK)_49") (pintype "bidirectional"))
    )
    (net (code "41") (name "/SWDIO") (class "Default")
      (node (ref "SWD1") (pin "2") (pinfunction "2_2") (pintype "passive"))
      (node (ref "U5") (pin "46") (pinfunction "PA13(JTMS-SWDIO)_46") (pintype "bidirectional"))
    )
    (net (code "42") (name "/TXD") (class "Default")
      (node (ref "U5") (pin "42") (pinfunction "PA9_42") (pintype "bidirectional"))
      (node (ref "U9") (pin "3") (pinfunction "RXD_3") (pintype "passive"))
    )
    (net (code "43") (name "/TXD2") (class "Default")
      (node (ref "U1") (pin "11") (pinfunction "T1IN_11") (pintype "input"))
      (node (ref "U5") (pin "16") (pinfunction "PA2_16") (pintype "bidirectional"))
    )
    (net (code "44") (name "/TXD2_Out") (class "Default")
      (node (ref "RS1") (pin "3") (pinfunction "3_3") (pintype "passive"))
      (node (ref "U1") (pin "14") (pinfunction "T1OUT_14") (pintype "output"))
    )
    (net (code "45") (name "/TXD3") (class "Default")
      (node (ref "U2") (pin "4") (pinfunction "DI_4") (pintype "input"))
      (node (ref "U5") (pin "51") (pinfunction "PC10_51") (pintype "bidirectional"))
    )
    (net (code "46") (name "/Vout0") (class "Default")
      (node (ref "DA1") (pin "1") (pinfunction "1_1") (pintype "passive"))
      (node (ref "R7") (pin "2") (pinfunction "2_2") (pintype "passive"))
      (node (ref "R9") (pin "1") (pinfunction "1_1") (pintype "passive"))
      (node (ref "U7") (pin "2") (pinfunction "-IN_2") (pintype "input"))
    )
    (net (code "47") (name "/Vout1") (class "Default")
      (node (ref "*3") (pin "15") (pinfunction "Vout_15") (pintype "passive"))
      (node (ref "*3") (pin "16") (pinfunction "Vout_16") (pintype "passive"))
      (node (ref "*3") (pin "6") (pinfunction "-IN_6") (pintype "passive"))
      (node (ref "DA2") (pin "1") (pinfunction "1_1") (pintype "passive"))
    )
    (net (code "48") (name "2.5V") (class "Default")
      (node (ref "*1") (pin "17") (pinfunction "REFIN_17") (pintype "passive"))
      (node (ref "*2") (pin "2") (pinfunction "V+_2") (pintype "passive"))
      (node (ref "C6") (pin "2") (pinfunction "2_2") (pintype "passive"))
      (node (ref "R2") (pin "1") (pinfunction "1_1") (pintype "passive"))
    )
    (net (code "49") (name "3.3V") (class "Default")
      (node (ref "*10") (pin "5") (pinfunction "VDD_5") (pintype "passive"))
      (node (ref "C28") (pin "2") (pinfunction "2_2") (pintype "passive"))
      (node (ref "C29") (pin "2") (pinfunction "2_2") (pintype "passive"))
      (node (ref "C50") (pin "1") (pinfunction "1_1") (pintype "passive"))
      (node (ref "C51") (pin "1") (pinfunction "1_1") (pintype "passive"))
      (node (ref "C53") (pin "1") (pinfunction "1_1") (pintype "passive"))
      (node (ref "C54") (pin "1") (pinfunction "1_1") (pintype "passive"))
      (node (ref "L4") (pin "2") (pinfunction "2_2") (pintype "passive"))
      (node (ref "R16") (pin "2") (pinfunction "2_2") (pintype "passive"))
      (node (ref "R17") (pin "2") (pinfunction "2_2") (pintype "passive"))
      (node (ref "R21") (pin "2") (pinfunction "2_2") (pintype "passive"))
      (node (ref "R22") (pin "2") (pinfunction "2_2") (pintype "passive"))
      (node (ref "R23") (pin "2") (pinfunction "2_2") (pintype "passive"))
      (node (ref "R25") (pin "2") (pinfunction "2_2") (pintype "passive"))
      (node (ref "R26") (pin "1") (pinfunction "1_1") (pintype "passive"))
      (node (ref "R3") (pin "1") (pinfunction "1_1") (pintype "passive"))
      (node (ref "R4") (pin "1") (pinfunction "1_1") (pintype "passive"))
      (node (ref "R5") (pin "1") (pinfunction "1_1") (pintype "passive"))
      (node (ref "U5") (pin "1") (pinfunction "VBAT_1") (pintype "power_in"))
      (node (ref "U5") (pin "19") (pinfunction "VDD_19") (pintype "power_in"))
      (node (ref "U5") (pin "32") (pinfunction "VDD_32") (pintype "power_in"))
      (node (ref "U5") (pin "48") (pinfunction "VDD_48") (pintype "power_in"))
      (node (ref "U5") (pin "64") (pinfunction "VDD_64") (pintype "power_in"))
      (node (ref "VR1") (pin "2") (pinfunction "Vout_2") (pintype "passive"))
    )
    (net (code "50") (name "GND") (class "Default")
      (node (ref "*1") (pin "15") (pinfunction "GND_15") (pintype "passive"))
      (node (ref "*10") (pin "2") (pinfunction "VSS_2") (pintype "passive"))
      (node (ref "*5") (pin "2") (pinfunction "2_2") (pintype "passive"))
      (node (ref "C1") (pin "1") (pinfunction "1_1") (pintype "passive"))
      (node (ref "C18") (pin "2") (pinfunction "2_2") (pintype "passive"))
      (node (ref "C19") (pin "1") (pinfunction "1_1") (pintype "passive"))
      (node (ref "C20") (pin "2") (pinfunction "2_2") (pintype "passive"))
      (node (ref "C22") (pin "1") (pinfunction "1_1") (pintype "passive"))
      (node (ref "C23") (pin "2") (pinfunction "2_2") (pintype "passive"))
      (node (ref "C26") (pin "1") (pinfunction "1_1") (pintype "passive"))
      (node (ref "C27") (pin "1") (pinfunction "1_1") (pintype "passive"))
      (node (ref "C28") (pin "1") (pinfunction "1_1") (pintype "passive"))
      (node (ref "C29") (pin "1") (pinfunction "1_1") (pintype "passive"))
      (node (ref "C3") (pin "2") (pinfunction "2_2") (pintype "passive"))
      (node (ref "C39") (pin "2") (pinfunction "2_2") (pintype "passive"))
      (node (ref "C40") (pin "2") (pinfunction "2_2") (pintype "passive"))
      (node (ref "C41") (pin "2") (pinfunction "2_2") (pintype "passive"))
      (node (ref "C42") (pin "1") (pinfunction "1_1") (pintype "passive"))
      (node (ref "C43") (pin "2") (pinfunction "2_2") (pintype "passive"))
      (node (ref "C45") (pin "1") (pinfunction "1_1") (pintype "passive"))
      (node (ref "C46") (pin "1") (pinfunction "1_1") (pintype "passive"))
      (node (ref "C47") (pin "1") (pinfunction "1_1") (pintype "passive"))
      (node (ref "C48") (pin "1") (pinfunction "1_1") (pintype "passive"))
      (node (ref "C49") (pin "1") (pinfunction "1_1") (pintype "passive"))
      (node (ref "C5") (pin "2") (pinfunction "2_2") (pintype "passive"))
      (node (ref "C50") (pin "2") (pinfunction "2_2") (pintype "passive"))
      (node (ref "C51") (pin "2") (pinfunction "2_2") (pintype "passive"))
      (node (ref "C52") (pin "2") (pinfunction "2_2") (pintype "passive"))
      (node (ref "C53") (pin "2") (pinfunction "2_2") (pintype "passive"))
      (node (ref "C54") (pin "2") (pinfunction "2_2") (pintype "passive"))
      (node (ref "C7") (pin "1") (pinfunction "1_1") (pintype "passive"))
      (node (ref "C8") (pin "2") (pinfunction "2_2") (pintype "passive"))
      (node (ref "C9") (pin "2") (pinfunction "2_2") (pintype "passive"))
      (node (ref "D1") (pin "1") (pinfunction "A_1") (pintype "passive"))
      (node (ref "D7") (pin "1") (pinfunction "A_1") (pintype "passive"))
      (node (ref "D8") (pin "2") (pinfunction "K_2") (pintype "passive"))
      (node (ref "D9") (pin "K") (pinfunction "K_K") (pintype "passive"))
      (node (ref "L2") (pin "2") (pinfunction "2_2") (pintype "passive"))
      (node (ref "L3") (pin "1") (pinfunction "1_1") (pintype "passive"))
      (node (ref "R27") (pin "1") (pinfunction "1_1") (pintype "passive"))
      (node (ref "RESET1") (pin "2") (pinfunction "2_2") (pintype "passive"))
      (node (ref "RS1") (pin "4") (pinfunction "4_4") (pintype "passive"))
      (node (ref "RS2") (pin "3") (pinfunction "3_3") (pintype "passive"))
      (node (ref "S1") (pin "2") (pinfunction "2_2") (pintype "passive"))
      (node (ref "SWD1") (pin "3") (pinfunction "3_3") (pintype "passive"))
      (node (ref "U1") (pin "15") (pinfunction "GND_15") (pintype "power_in"))
      (node (ref "U10") (pin "2") (pinfunction "GND_2") (pintype "passive"))
      (node (ref "U10") (pin "8") (pinfunction "S_8") (pintype "passive"))
      (node (ref "U2") (pin "5") (pinfunction "GND_5") (pintype "power_in"))
      (node (ref "U3") (pin "3") (pinfunction "GND_3") (pintype "power_in"))
      (node (ref "U3") (pin "5") (pinfunction "~{ON}/OFF_5") (pintype "input"))
      (node (ref "U3") (pin "6") (pinfunction "6_6") (pintype "power_in"))
      (node (ref "U4") (pin "4") (pinfunction "FB_4") (pintype "input"))
      (node (ref "U5") (pin "12") (pinfunction "VSSA_12") (pintype "power_in"))
      (node (ref "U5") (pin "18") (pinfunction "VSS_18") (pintype "power_in"))
      (node (ref "U5") (pin "63") (pinfunction "VSS_63") (pintype "power_in"))
      (node (ref "U9") (pin "1") (pinfunction "GND_1") (pintype "passive"))
      (node (ref "USB_USART1") (pin "5") (pinfunction "VSS_5") (pintype "passive"))
      (node (ref "VR1") (pin "1") (pinfunction "GND_1") (pintype "passive"))
    )
    (net (code "51") (name "Net-(*3-E{slash}S#)") (class "Default")
      (node (ref "*3") (pin "4") (pinfunction "E/S#_4") (pintype "passive"))
      (node (ref "*3") (pin "7") (pinfunction "Vdig_7") (pintype "passive"))
      (node (ref "D5") (pin "2") (pinfunction "K_2") (pintype "passive"))
      (node (ref "R6") (pin "1") (pinfunction "1_1") (pintype "passive"))
    )
    (net (code "52") (name "Net-(*3-Iset)") (class "Default")
      (node (ref "*3") (pin "9") (pinfunction "Iset_9") (pintype "passive"))
      (node (ref "C24") (pin "2") (pinfunction "2_2") (pintype "passive"))
      (node (ref "R10") (pin "2") (pinfunction "2_2") (pintype "passive"))
    )
    (net (code "53") (name "Net-(*4--IN)") (class "Default")
      (node (ref "*4") (pin "15") (pinfunction "Vout_15") (pintype "passive"))
      (node (ref "*4") (pin "16") (pinfunction "Vout_16") (pintype "passive"))
      (node (ref "*4") (pin "6") (pinfunction "-IN_6") (pintype "passive"))
      (node (ref "R7") (pin "1") (pinfunction "1_1") (pintype "passive"))
      (node (ref "U7") (pin "3") (pinfunction "+IN_3") (pintype "input"))
    )
    (net (code "54") (name "Net-(*4-E{slash}S#)") (class "Default")
      (node (ref "*4") (pin "4") (pinfunction "E/S#_4") (pintype "passive"))
      (node (ref "*4") (pin "7") (pinfunction "Vdig_7") (pintype "passive"))
      (node (ref "D6") (pin "2") (pinfunction "K_2") (pintype "passive"))
      (node (ref "R8") (pin "1") (pinfunction "1_1") (pintype "passive"))
    )
    (net (code "55") (name "Net-(*4-Iset)") (class "Default")
      (node (ref "*4") (pin "9") (pinfunction "Iset_9") (pintype "passive"))
      (node (ref "C25") (pin "2") (pinfunction "2_2") (pintype "passive"))
      (node (ref "R11") (pin "2") (pinfunction "2_2") (pintype "passive"))
    )
    (net (code "56") (name "Net-(*6-V+)") (class "Default")
      (node (ref "*6") (pin "2") (pinfunction "V+_2") (pintype "passive"))
      (node (ref "C30") (pin "2") (pinfunction "2_2") (pintype "passive"))
      (node (ref "R18") (pin "1") (pinfunction "1_1") (pintype "passive"))
      (node (ref "U7") (pin "5") (pinfunction "REF_5") (pintype "input"))
    )
    (net (code "57") (name "Net-(*7-V+)") (class "Default")
      (node (ref "*7") (pin "2") (pinfunction "V+_2") (pintype "passive"))
      (node (ref "C31") (pin "2") (pinfunction "2_2") (pintype "passive"))
      (node (ref "R19") (pin "1") (pinfunction "1_1") (pintype "passive"))
      (node (ref "U8") (pin "5") (pinfunction "REF_5") (pintype "input"))
    )
    (net (code "58") (name "Net-(*8-V+)") (class "Default")
      (node (ref "*8") (pin "2") (pinfunction "V+_2") (pintype "passive"))
      (node (ref "C32") (pin "2") (pinfunction "2_2") (pintype "passive"))
      (node (ref "R20") (pin "1") (pinfunction "1_1") (pintype "passive"))
      (node (ref "U6") (pin "5") (pinfunction "REF_5") (pintype "input"))
    )
    (net (code "59") (name "Net-(D1-K)") (class "Default")
      (node (ref "D1") (pin "2") (pinfunction "K_2") (pintype "passive"))
      (node (ref "L1") (pin "1") (pinfunction "1_1") (pintype "passive"))
      (node (ref "U3") (pin "2") (pinfunction "OUT_2") (pintype "power_in"))
    )
    (net (code "60") (name "Net-(D2-PadA)") (class "Default")
      (node (ref "D2") (pin "A") (pinfunction "A_A") (pintype "passive"))
      (node (ref "R3") (pin "2") (pinfunction "2_2") (pintype "passive"))
    )
    (net (code "61") (name "Net-(D3-PadA)") (class "Default")
      (node (ref "D3") (pin "A") (pinfunction "A_A") (pintype "passive"))
      (node (ref "R4") (pin "2") (pinfunction "2_2") (pintype "passive"))
    )
    (net (code "62") (name "Net-(D4-K)") (class "Default")
      (node (ref "D4") (pin "2") (pinfunction "K_2") (pintype "passive"))
      (node (ref "L2") (pin "1") (pinfunction "1_1") (pintype "passive"))
      (node (ref "U4") (pin "2") (pinfunction "OUT_2") (pintype "power_in"))
    )
    (net (code "63") (name "Net-(D9-PadA)") (class "Default")
      (node (ref "D9") (pin "A") (pinfunction "A_A") (pintype "passive"))
      (node (ref "R24") (pin "2") (pinfunction "2_2") (pintype "passive"))
    )
    (net (code "64") (name "Net-(R13-Pad1)") (class "Default")
      (node (ref "R13") (pin "1") (pinfunction "1_1") (pintype "passive"))
      (node (ref "U8") (pin "1") (pinfunction "RG_1") (pintype "passive"))
    )
    (net (code "65") (name "Net-(R13-Pad2)") (class "Default")
      (node (ref "R13") (pin "2") (pinfunction "2_2") (pintype "passive"))
      (node (ref "U8") (pin "8") (pinfunction "RG_8") (pintype "passive"))
    )
    (net (code "66") (name "Net-(R14-Pad1)") (class "Default")
      (node (ref "R14") (pin "1") (pinfunction "1_1") (pintype "passive"))
      (node (ref "U7") (pin "1") (pinfunction "RG_1") (pintype "passive"))
    )
    (net (code "67") (name "Net-(R14-Pad2)") (class "Default")
      (node (ref "R14") (pin "2") (pinfunction "2_2") (pintype "passive"))
      (node (ref "U7") (pin "8") (pinfunction "RG_8") (pintype "passive"))
    )
    (net (code "68") (name "Net-(R15-Pad1)") (class "Default")
      (node (ref "R15") (pin "1") (pinfunction "1_1") (pintype "passive"))
      (node (ref "U6") (pin "1") (pinfunction "RG_1") (pintype "passive"))
    )
    (net (code "69") (name "Net-(R15-Pad2)") (class "Default")
      (node (ref "R15") (pin "2") (pinfunction "2_2") (pintype "passive"))
      (node (ref "U6") (pin "8") (pinfunction "RG_8") (pintype "passive"))
    )
    (net (code "70") (name "Net-(U1-C1+)") (class "Default")
      (node (ref "C2") (pin "2") (pinfunction "2_2") (pintype "passive"))
      (node (ref "U1") (pin "1") (pinfunction "C1+_1") (pintype "passive"))
    )
    (net (code "71") (name "Net-(U1-C1-)") (class "Default")
      (node (ref "C2") (pin "1") (pinfunction "1_1") (pintype "passive"))
      (node (ref "U1") (pin "3") (pinfunction "C1-_3") (pintype "passive"))
    )
    (net (code "72") (name "Net-(U1-C2+)") (class "Default")
      (node (ref "C4") (pin "1") (pinfunction "1_1") (pintype "passive"))
      (node (ref "U1") (pin "4") (pinfunction "C2+_4") (pintype "passive"))
    )
    (net (code "73") (name "Net-(U1-C2-)") (class "Default")
      (node (ref "C4") (pin "2") (pinfunction "2_2") (pintype "passive"))
      (node (ref "U1") (pin "5") (pinfunction "C2-_5") (pintype "passive"))
    )
    (net (code "74") (name "Net-(U1-V+)") (class "Default")
      (node (ref "C5") (pin "1") (pinfunction "1_1") (pintype "passive"))
      (node (ref "U1") (pin "2") (pinfunction "V+_2") (pintype "power_in"))
    )
    (net (code "75") (name "Net-(U1-V-)") (class "Default")
      (node (ref "C8") (pin "1") (pinfunction "1_1") (pintype "passive"))
      (node (ref "U1") (pin "6") (pinfunction "V-_6") (pintype "power_in"))
    )
    (net (code "76") (name "Net-(U5A-BOOT0)") (class "Default")
      (node (ref "R27") (pin "2") (pinfunction "2_2") (pintype "passive"))
      (node (ref "U5") (pin "60") (pinfunction "BOOT0_60") (pintype "input"))
    )
    (net (code "77") (name "Net-(U5A-VCAP_1)") (class "Default")
      (node (ref "C40") (pin "1") (pinfunction "1_1") (pintype "passive"))
      (node (ref "U5") (pin "31") (pinfunction "VCAP_1_31") (pintype "power_in"))
    )
    (net (code "78") (name "Net-(U5A-VCAP_2)") (class "Default")
      (node (ref "C41") (pin "1") (pinfunction "1_1") (pintype "passive"))
      (node (ref "U5") (pin "47") (pinfunction "VCAP_2_47") (pintype "power_in"))
    )
    (net (code "79") (name "Net-(U5B-VDDA)") (class "Default")
      (node (ref "C52") (pin "1") (pinfunction "1_1") (pintype "passive"))
      (node (ref "L4") (pin "1") (pinfunction "1_1") (pintype "passive"))
      (node (ref "U5") (pin "13") (pinfunction "VDDA_13") (pintype "power_in"))
    )
    (net (code "80") (name "Net-(U8-+IN)") (class "Default")
      (node (ref "R12") (pin "1") (pinfunction "1_1") (pintype "passive"))
      (node (ref "R9") (pin "2") (pinfunction "2_2") (pintype "passive"))
      (node (ref "U8") (pin "3") (pinfunction "+IN_3") (pintype "input"))
    )
    (net (code "81") (name "Net-(U9-V3.3)") (class "Default")
      (node (ref "C43") (pin "1") (pinfunction "1_1") (pintype "passive"))
      (node (ref "U9") (pin "4") (pinfunction "V3.3_4") (pintype "passive"))
    )
    (net (code "82") (name "Net-(U9-XI)") (class "Default")
      (node (ref "C45") (pin "2") (pinfunction "2_2") (pintype "passive"))
      (node (ref "U9") (pin "7") (pinfunction "XI_7") (pintype "passive"))
      (node (ref "Y1") (pin "1") (pinfunction "OSC1_1") (pintype "passive"))
    )
    (net (code "83") (name "Net-(U9-XO)") (class "Default")
      (node (ref "C46") (pin "2") (pinfunction "2_2") (pintype "passive"))
      (node (ref "U9") (pin "8") (pinfunction "XO_8") (pintype "passive"))
      (node (ref "Y1") (pin "3") (pinfunction "OSC2_3") (pintype "passive"))
    )
    (net (code "84") (name "SGND") (class "Default")
      (node (ref "*1") (pin "18") (pinfunction "DAC_GND_18") (pintype "passive"))
      (node (ref "*1") (pin "19") (pinfunction "DAC_GND_19") (pintype "passive"))
      (node (ref "*1") (pin "20") (pinfunction "SIG_GND_20") (pintype "passive"))
      (node (ref "*1") (pin "21") (pinfunction "SIG_GND_21") (pintype "passive"))
      (node (ref "*2") (pin "1") (pinfunction "V-_1") (pintype "passive"))
      (node (ref "*6") (pin "1") (pinfunction "V-_1") (pintype "passive"))
      (node (ref "*7") (pin "1") (pinfunction "V-_1") (pintype "passive"))
      (node (ref "*8") (pin "1") (pinfunction "V-_1") (pintype "passive"))
      (node (ref "*9") (pin "1") (pinfunction "ADDR_1") (pintype "passive"))
      (node (ref "*9") (pin "3") (pinfunction "GND_3") (pintype "passive"))
      (node (ref "*9") (pin "7") (pinfunction "AIN3_7") (pintype "passive"))
      (node (ref "C10") (pin "2") (pinfunction "2_2") (pintype "passive"))
      (node (ref "C11") (pin "1") (pinfunction "1_1") (pintype "passive"))
      (node (ref "C12") (pin "1") (pinfunction "1_1") (pintype "passive"))
      (node (ref "C13") (pin "1") (pinfunction "1_1") (pintype "passive"))
      (node (ref "C14") (pin "2") (pinfunction "2_2") (pintype "passive"))
      (node (ref "C15") (pin "1") (pinfunction "1_1") (pintype "passive"))
      (node (ref "C16") (pin "1") (pinfunction "1_1") (pintype "passive"))
      (node (ref "C17") (pin "1") (pinfunction "1_1") (pintype "passive"))
      (node (ref "C30") (pin "1") (pinfunction "1_1") (pintype "passive"))
      (node (ref "C31") (pin "1") (pinfunction "1_1") (pintype "passive"))
      (node (ref "C32") (pin "1") (pinfunction "1_1") (pintype "passive"))
      (node (ref "C33") (pin "1") (pinfunction "1_1") (pintype "passive"))
      (node (ref "C34") (pin "1") (pinfunction "1_1") (pintype "passive"))
      (node (ref "C35") (pin "1") (pinfunction "1_1") (pintype "passive"))
      (node (ref "C36") (pin "1") (pinfunction "1_1") (pintype "passive"))
      (node (ref "C37") (pin "1") (pinfunction "1_1") (pintype "passive"))
      (node (ref "C38") (pin "1") (pinfunction "1_1") (pintype "passive"))
      (node (ref "C44") (pin "2") (pinfunction "2_2") (pintype "passive"))
      (node (ref "C6") (pin "1") (pinfunction "1_1") (pintype "passive"))
      (node (ref "DA1") (pin "2") (pinfunction "2_2") (pintype "passive"))
      (node (ref "DA2") (pin "2") (pinfunction "2_2") (pintype "passive"))
      (node (ref "Force Sensor1") (pin "4") (pinfunction "4_4") (pintype "passive"))
      (node (ref "L3") (pin "2") (pinfunction "2_2") (pintype "passive"))
      (node (ref "R12") (pin "2") (pinfunction "2_2") (pintype "passive"))
      (node (ref "U8") (pin "2") (pinfunction "-IN_2") (pintype "input"))
    )
    (net (code "85") (name "unconnected-(*1-NC-Pad2)") (class "Default")
      (node (ref "*1") (pin "2") (pinfunction "NC_2") (pintype "passive"))
    )
    (net (code "86") (name "unconnected-(*1-NC-Pad4)") (class "Default")
      (node (ref "*1") (pin "4") (pinfunction "NC_4") (pintype "passive"))
    )
    (net (code "87") (name "unconnected-(*1-NC-Pad6)") (class "Default")
      (node (ref "*1") (pin "6") (pinfunction "NC_6") (pintype "passive"))
    )
    (net (code "88") (name "unconnected-(*1-NC-Pad12)") (class "Default")
      (node (ref "*1") (pin "12") (pinfunction "NC_12") (pintype "passive"))
    )
    (net (code "89") (name "unconnected-(*1-NC-Pad13)") (class "Default")
      (node (ref "*1") (pin "13") (pinfunction "NC_13") (pintype "passive"))
    )
    (net (code "90") (name "unconnected-(*1-NC-Pad22)") (class "Default")
      (node (ref "*1") (pin "22") (pinfunction "NC_22") (pintype "passive"))
    )
    (net (code "91") (name "unconnected-(*2-ADJ-Pad3)") (class "Default")
      (node (ref "*2") (pin "3") (pinfunction "ADJ_3") (pintype "passive"))
    )
    (net (code "92") (name "unconnected-(*3-Iflag-Pad8)") (class "Default")
      (node (ref "*3") (pin "8") (pinfunction "Iflag_8") (pintype "passive"))
    )
    (net (code "93") (name "unconnected-(*3-Tflag-Pad3)") (class "Default")
      (node (ref "*3") (pin "3") (pinfunction "Tflag_3") (pintype "passive"))
    )
    (net (code "94") (name "unconnected-(*3-Tsense-Pad12)") (class "Default")
      (node (ref "*3") (pin "12") (pinfunction "Tsense_12") (pintype "passive"))
    )
    (net (code "95") (name "unconnected-(*4-Iflag-Pad8)") (class "Default")
      (node (ref "*4") (pin "8") (pinfunction "Iflag_8") (pintype "passive"))
    )
    (net (code "96") (name "unconnected-(*4-Tflag-Pad3)") (class "Default")
      (node (ref "*4") (pin "3") (pinfunction "Tflag_3") (pintype "passive"))
    )
    (net (code "97") (name "unconnected-(*4-Tsense-Pad12)") (class "Default")
      (node (ref "*4") (pin "12") (pinfunction "Tsense_12") (pintype "passive"))
    )
    (net (code "98") (name "unconnected-(*6-ADJ-Pad3)") (class "Default")
      (node (ref "*6") (pin "3") (pinfunction "ADJ_3") (pintype "passive"))
    )
    (net (code "99") (name "unconnected-(*7-ADJ-Pad3)") (class "Default")
      (node (ref "*7") (pin "3") (pinfunction "ADJ_3") (pintype "passive"))
    )
    (net (code "100") (name "unconnected-(*8-ADJ-Pad3)") (class "Default")
      (node (ref "*8") (pin "3") (pinfunction "ADJ_3") (pintype "passive"))
    )
    (net (code "101") (name "unconnected-(*10-NC-Pad3)") (class "Default")
      (node (ref "*10") (pin "3") (pinfunction "NC_3") (pintype "passive"))
    )
    (net (code "102") (name "unconnected-(*10-NC-Pad4)") (class "Default")
      (node (ref "*10") (pin "4") (pinfunction "NC_4") (pintype "passive"))
    )
    (net (code "103") (name "unconnected-(RS1-Pad1)") (class "Default")
      (node (ref "RS1") (pin "1") (pinfunction "1_1") (pintype "passive"))
    )
    (net (code "104") (name "unconnected-(RS1-Pad2)") (class "Default")
      (node (ref "RS1") (pin "2") (pinfunction "2_2") (pintype "passive"))
    )
    (net (code "105") (name "unconnected-(RS1-Pad6)") (class "Default")
      (node (ref "RS1") (pin "6") (pinfunction "6_6") (pintype "passive"))
    )
    (net (code "106") (name "unconnected-(T1-Pad1)") (class "Default")
      (node (ref "T1") (pin "1") (pinfunction "1_1") (pintype "passive"))
    )
    (net (code "107") (name "unconnected-(T2-Pad1)") (class "Default")
      (node (ref "T2") (pin "1") (pinfunction "1_1") (pintype "passive"))
    )
    (net (code "108") (name "unconnected-(T3-Pad1)") (class "Default")
      (node (ref "T3") (pin "1") (pinfunction "1_1") (pintype "passive"))
    )
    (net (code "109") (name "unconnected-(T4-Pad1)") (class "Default")
      (node (ref "T4") (pin "1") (pinfunction "1_1") (pintype "passive"))
    )
    (net (code "110") (name "unconnected-(U1-R2IN-Pad8)") (class "Default")
      (node (ref "U1") (pin "8") (pinfunction "R2IN_8") (pintype "input+no_connect"))
    )
    (net (code "111") (name "unconnected-(U1-R2OUT-Pad9)") (class "Default")
      (node (ref "U1") (pin "9") (pinfunction "R2OUT_9") (pintype "output"))
    )
    (net (code "112") (name "unconnected-(U1-T2IN-Pad10)") (class "Default")
      (node (ref "U1") (pin "10") (pinfunction "T2IN_10") (pintype "input+no_connect"))
    )
    (net (code "113") (name "unconnected-(U1-T2OUT-Pad7)") (class "Default")
      (node (ref "U1") (pin "7") (pinfunction "T2OUT_7") (pintype "output"))
    )
    (net (code "114") (name "unconnected-(U5A-PA0-WKUP(PA0)-Pad14)") (class "Default")
      (node (ref "U5") (pin "14") (pinfunction "PA0-WKUP(PA0)_14") (pintype "bidirectional"))
    )
    (net (code "115") (name "unconnected-(U5A-PA1-Pad15)") (class "Default")
      (node (ref "U5") (pin "15") (pinfunction "PA1_15") (pintype "bidirectional"))
    )
    (net (code "116") (name "unconnected-(U5A-PA4-Pad20)") (class "Default")
      (node (ref "U5") (pin "20") (pinfunction "PA4_20") (pintype "bidirectional"))
    )
    (net (code "117") (name "unconnected-(U5A-PA5-Pad21)") (class "Default")
      (node (ref "U5") (pin "21") (pinfunction "PA5_21") (pintype "bidirectional"))
    )
    (net (code "118") (name "unconnected-(U5A-PA6-Pad22)") (class "Default")
      (node (ref "U5") (pin "22") (pinfunction "PA6_22") (pintype "bidirectional"))
    )
    (net (code "119") (name "unconnected-(U5A-PA7-Pad23)") (class "Default")
      (node (ref "U5") (pin "23") (pinfunction "PA7_23") (pintype "bidirectional"))
    )
    (net (code "120") (name "unconnected-(U5A-PA8-Pad41)") (class "Default")
      (node (ref "U5") (pin "41") (pinfunction "PA8_41") (pintype "bidirectional"))
    )
    (net (code "121") (name "unconnected-(U5A-PA15(JTDI)-Pad50)") (class "Default")
      (node (ref "U5") (pin "50") (pinfunction "PA15(JTDI)_50") (pintype "bidirectional"))
    )
    (net (code "122") (name "unconnected-(U5A-PB0-Pad26)") (class "Default")
      (node (ref "U5") (pin "26") (pinfunction "PB0_26") (pintype "bidirectional"))
    )
    (net (code "123") (name "unconnected-(U5A-PB1-Pad27)") (class "Default")
      (node (ref "U5") (pin "27") (pinfunction "PB1_27") (pintype "bidirectional"))
    )
    (net (code "124") (name "unconnected-(U5A-PB2-BOOT1(PB2)-Pad28)") (class "Default")
      (node (ref "U5") (pin "28") (pinfunction "PB2-BOOT1(PB2)_28") (pintype "bidirectional"))
    )
    (net (code "125") (name "unconnected-(U5A-PB3(JTDO{slash}TRACESWO)-Pad55)") (class "Default")
      (node (ref "U5") (pin "55") (pinfunction "PB3(JTDO/TRACESWO)_55") (pintype "bidirectional"))
    )
    (net (code "126") (name "unconnected-(U5A-PB4(NJTRST)-Pad56)") (class "Default")
      (node (ref "U5") (pin "56") (pinfunction "PB4(NJTRST)_56") (pintype "bidirectional"))
    )
    (net (code "127") (name "unconnected-(U5A-PB8-Pad61)") (class "Default")
      (node (ref "U5") (pin "61") (pinfunction "PB8_61") (pintype "bidirectional"))
    )
    (net (code "128") (name "unconnected-(U5A-PB9-Pad62)") (class "Default")
      (node (ref "U5") (pin "62") (pinfunction "PB9_62") (pintype "bidirectional"))
    )
    (net (code "129") (name "unconnected-(U5A-PC3-Pad11)") (class "Default")
      (node (ref "U5") (pin "11") (pinfunction "PC3_11") (pintype "bidirectional"))
    )
    (net (code "130") (name "unconnected-(U5A-PC4-Pad24)") (class "Default")
      (node (ref "U5") (pin "24") (pinfunction "PC4_24") (pintype "bidirectional"))
    )
    (net (code "131") (name "unconnected-(U5A-PC5-Pad25)") (class "Default")
      (node (ref "U5") (pin "25") (pinfunction "PC5_25") (pintype "bidirectional"))
    )
    (net (code "132") (name "unconnected-(U5A-PC6-Pad37)") (class "Default")
      (node (ref "U5") (pin "37") (pinfunction "PC6_37") (pintype "bidirectional"))
    )
    (net (code "133") (name "unconnected-(U5A-PC7-Pad38)") (class "Default")
      (node (ref "U5") (pin "38") (pinfunction "PC7_38") (pintype "bidirectional"))
    )
    (net (code "134") (name "unconnected-(U5A-PC8-Pad39)") (class "Default")
      (node (ref "U5") (pin "39") (pinfunction "PC8_39") (pintype "bidirectional"))
    )
    (net (code "135") (name "unconnected-(U5A-PC9-Pad40)") (class "Default")
      (node (ref "U5") (pin "40") (pinfunction "PC9_40") (pintype "bidirectional"))
    )
    (net (code "136") (name "unconnected-(U5A-PC12-Pad53)") (class "Default")
      (node (ref "U5") (pin "53") (pinfunction "PC12_53") (pintype "bidirectional"))
    )
    (net (code "137") (name "unconnected-(U5A-PC13-Pad2)") (class "Default")
      (node (ref "U5") (pin "2") (pinfunction "PC13_2") (pintype "bidirectional"))
    )
    (net (code "138") (name "unconnected-(U5A-PC14-OSC32_IN(PC14)-Pad3)") (class "Default")
      (node (ref "U5") (pin "3") (pinfunction "PC14-OSC32_IN(PC14)_3") (pintype "bidirectional"))
    )
    (net (code "139") (name "unconnected-(U5A-PC15-OSC32_OUT(PC15)-Pad4)") (class "Default")
      (node (ref "U5") (pin "4") (pinfunction "PC15-OSC32_OUT(PC15)_4") (pintype "bidirectional"))
    )
    (net (code "140") (name "unconnected-(U9-CTS#-Pad9)") (class "Default")
      (node (ref "U9") (pin "9") (pinfunction "CTS#_9") (pintype "passive"))
    )
    (net (code "141") (name "unconnected-(U9-DCD#-Pad13)") (class "Default")
      (node (ref "U9") (pin "13") (pinfunction "DCD#_13") (pintype "passive"))
    )
    (net (code "142") (name "unconnected-(U9-DSR#-Pad10)") (class "Default")
      (node (ref "U9") (pin "10") (pinfunction "DSR#_10") (pintype "passive"))
    )
    (net (code "143") (name "unconnected-(U9-DTR#-Pad12)") (class "Default")
      (node (ref "U9") (pin "12") (pinfunction "DTR#_12") (pintype "passive"))
    )
    (net (code "144") (name "unconnected-(U9-R232-Pad15)") (class "Default")
      (node (ref "U9") (pin "15") (pinfunction "R232_15") (pintype "passive"))
    )
    (net (code "145") (name "unconnected-(U9-RI#-Pad14)") (class "Default")
      (node (ref "U9") (pin "14") (pinfunction "RI#_14") (pintype "passive"))
    )
    (net (code "146") (name "unconnected-(U9-RTS#-Pad11)") (class "Default")
      (node (ref "U9") (pin "11") (pinfunction "RTS#_11") (pintype "passive"))
    )
    (net (code "147") (name "unconnected-(U10-n.c.-Pad5)") (class "Default")
      (node (ref "U10") (pin "5") (pinfunction "n.c._5") (pintype "passive"))
    )
    (net (code "148") (name "unconnected-(USB_USART1-ID-Pad4)") (class "Default")
      (node (ref "USB_USART1") (pin "4") (pinfunction "ID_4") (pintype "passive"))
    )
  )
)
